# 1_ISO-RS485.net
KiCad netlist of a schematic drawn in Altium Designer
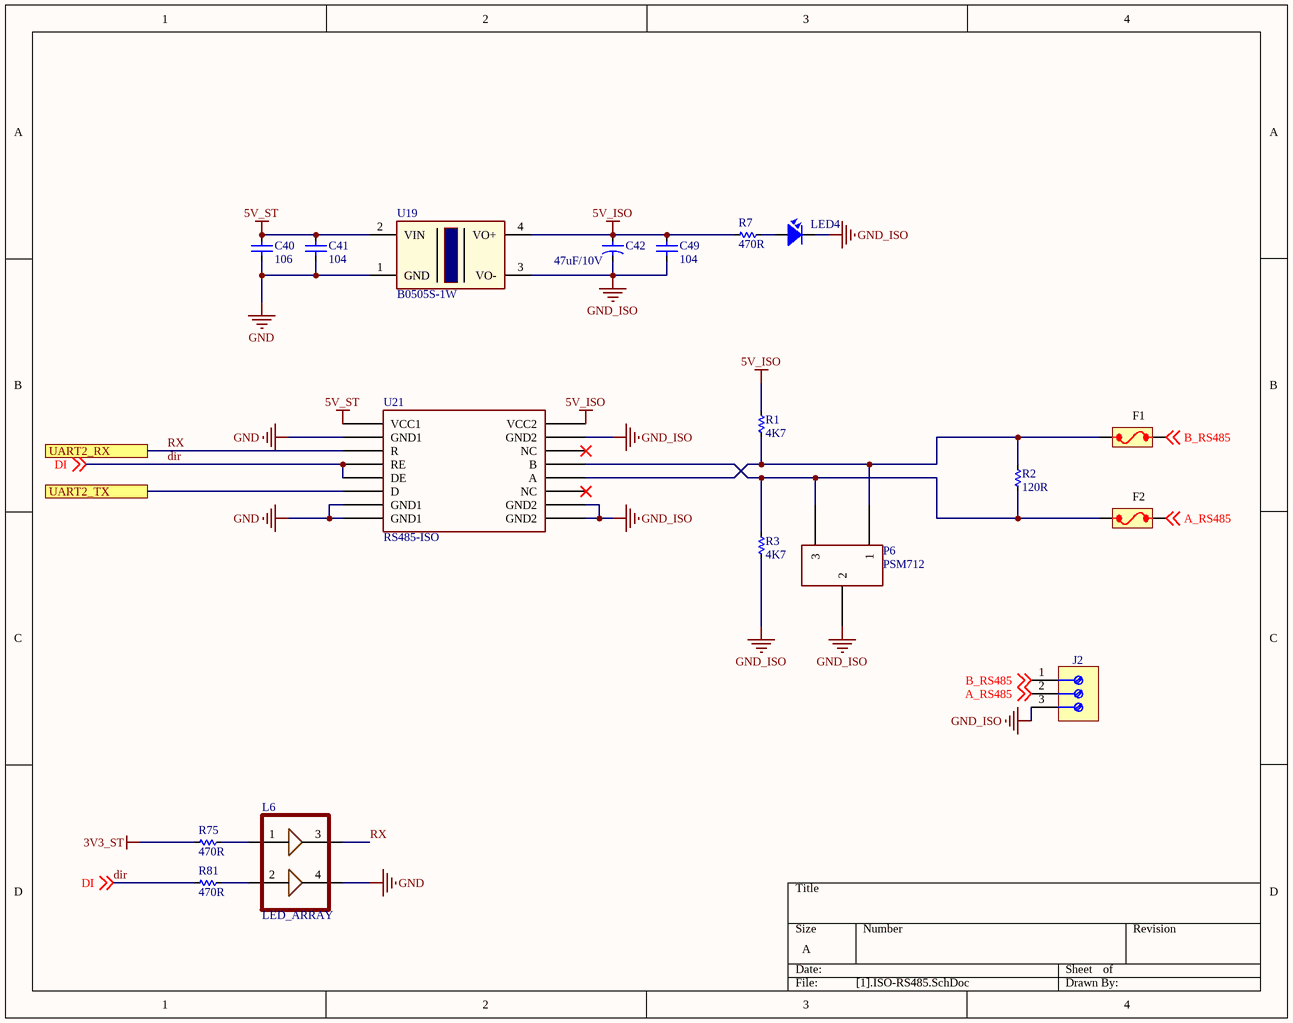
[diagram p0: [1].ISO-RS485.SchDoc]

(export (version "E")
  (design (tool "Eeschema 10.0.6"))
  (components
    (comp (ref "C40")
      (value "106")
      (footprint "CAP-1206-SC")
      (libsource (lib "QT TECH CO.,LTD") (part "CAP_NP"))
    )
    (comp (ref "C41")
      (value "104")
      (footprint "CAP-1206-SC")
      (libsource (lib "QT TECH CO.,LTD") (part "CAP_NP"))
    )
    (comp (ref "C42")
      (value "47uF/10V")
      (footprint "CAP 6.3X12X2.5")
      (libsource (lib "QT TECH CO.,LTD") (part "CAP 100uF/16V"))
    )
    (comp (ref "C49")
      (value "104")
      (footprint "CAP-1206-SC")
      (libsource (lib "QT TECH CO.,LTD") (part "CAP_NP"))
    )
    (comp (ref "F1")
      (value "FUSE")
      (footprint "FUSE_RESETTABLE_SMD_1812")
      (fields (field (name "PUBLISHER") "Hoang Nguyen"))
      (libsource (lib "Nucleo_IOT") (part "FUSE"))
    )
    (comp (ref "F2")
      (value "FUSE")
      (footprint "FUSE_RESETTABLE_SMD_1812")
      (fields (field (name "PUBLISHER") "Hoang Nguyen"))
      (libsource (lib "Nucleo_IOT") (part "FUSE"))
    )
    (comp (ref "J2")
      (value "~")
      (footprint "PHOENIX_1803439")
      (description "Terminal Block, 3 Positions, Screw Connection")
      (libsource (lib "SCH_NHATBON") (part "Terminal Block_3 Positions_Screw Connection"))
    )
    (comp (ref "L6")
      (value "LED_ARRAY")
      (footprint "LED_ARRAY2")
      (libsource (lib "LED_ARRAY_2") (part "LED_ARRAY"))
    )
    (comp (ref "LED4")
      (value "LED RED 3mm")
      (footprint "LED-3MM-RED")
      (description "LED Single colour Green and Red")
      (libsource (lib "LIBRARY") (part "LED"))
    )
    (comp (ref "P6") (value "PSM712") (footprint "SOT23C") (libsource (lib "PSM712") (part "PSM712")))
    (comp (ref "R1")
      (value "4K7")
      (footprint "RES-SMD-0805")
      (description "Resistor")
      (fields
        (field (name "MANUFACTURER") "Generic Components")
        (field (name "PUBLISHER") "Altium Hobart Technology Centre")
      )
      (libsource (lib "LIBRARY") (part "Res-SMD"))
    )
    (comp (ref "R2")
      (value "120R")
      (footprint "RES-SMD-0805")
      (description "Resistor")
      (fields
        (field (name "MANUFACTURER") "Generic Components")
        (field (name "PUBLISHER") "Altium Hobart Technology Centre")
      )
      (libsource (lib "LIBRARY") (part "Res-SMD"))
    )
    (comp (ref "R3")
      (value "4K7")
      (footprint "RES-SMD-0805")
      (description "Resistor")
      (fields
        (field (name "MANUFACTURER") "Generic Components")
        (field (name "PUBLISHER") "Altium Hobart Technology Centre")
      )
      (libsource (lib "LIBRARY") (part "Res-SMD"))
    )
    (comp (ref "R7")
      (value "470R")
      (footprint "RES-SMD-0805")
      (description "Resistor")
      (fields
        (field (name "MANUFACTURER") "Generic Components")
        (field (name "PUBLISHER") "Altium Hobart Technology Centre")
      )
      (libsource (lib "LIBRARY") (part "Res-SMD"))
    )
    (comp (ref "R75")
      (value "470R")
      (footprint "RES-SMD-0805")
      (description "Resistor")
      (fields
        (field (name "MANUFACTURER") "Generic Components")
        (field (name "PUBLISHER") "Altium Hobart Technology Centre")
      )
      (libsource (lib "LIBRARY") (part "Res-SMD"))
    )
    (comp (ref "R81")
      (value "470R")
      (footprint "RES-SMD-0805")
      (description "Resistor")
      (fields
        (field (name "MANUFACTURER") "Generic Components")
        (field (name "PUBLISHER") "Altium Hobart Technology Centre")
      )
      (libsource (lib "LIBRARY") (part "Res-SMD"))
    )
    (comp (ref "U19")
      (value "B0505S-1W")
      (footprint "B0505S_1W")
      (libsource (lib "Nucleo_IOT") (part "B0505S-1W"))
    )
    (comp (ref "U21")
      (value "RS485-ISO")
      (footprint "SOIC127P1030X265-16N")
      (libsource (lib "RS485ISO") (part "RS485-ISO"))
    )
  )
  (nets
    (net (code "1") (name "/RX") (class "Default")
      (node (ref "L6") (pin "3") (pinfunction "3_3") (pintype "passive"))
      (node (ref "U21") (pin "3") (pinfunction "R_3") (pintype "passive"))
    )
    (net (code "2") (name "/UART2_TX") (class "Default")
      (node (ref "U21") (pin "6") (pinfunction "D_6") (pintype "passive"))
    )
    (net (code "3") (name "3V3_ST") (class "Default")
      (node (ref "R75") (pin "2") (pinfunction "2_2") (pintype "passive"))
    )
    (net (code "4") (name "5V_ISO") (class "Default")
      (node (ref "C42") (pin "1") (pinfunction "1_1") (pintype "passive"))
      (node (ref "C49") (pin "1") (pinfunction "1_1") (pintype "passive"))
      (node (ref "R1") (pin "2") (pinfunction "2_2") (pintype "passive"))
      (node (ref "R7") (pin "2") (pinfunction "2_2") (pintype "passive"))
      (node (ref "U19") (pin "4") (pinfunction "VO+_4") (pintype "passive"))
      (node (ref "U21") (pin "16") (pinfunction "VCC2_16") (pintype "passive"))
    )
    (net (code "5") (name "5V_ST") (class "Default")
      (node (ref "C40") (pin "1") (pinfunction "1_1") (pintype "passive"))
      (node (ref "C41") (pin "1") (pinfunction "1_1") (pintype "passive"))
      (node (ref "U19") (pin "2") (pinfunction "VIN_2") (pintype "power_in"))
      (node (ref "U21") (pin "1") (pinfunction "VCC1_1") (pintype "passive"))
    )
    (net (code "6") (name "A_RS485") (class "Default")
      (node (ref "F2") (pin "2") (pinfunction "2_2") (pintype "passive"))
      (node (ref "J2") (pin "2") (pinfunction "2_2") (pintype "passive"))
    )
    (net (code "7") (name "B_RS485") (class "Default")
      (node (ref "F1") (pin "2") (pinfunction "2_2") (pintype "passive"))
      (node (ref "J2") (pin "1") (pinfunction "1_1") (pintype "passive"))
    )
    (net (code "8") (name "DI") (class "Default")
      (node (ref "R81") (pin "2") (pinfunction "2_2") (pintype "passive"))
      (node (ref "U21") (pin "4") (pinfunction "RE_4") (pintype "passive"))
      (node (ref "U21") (pin "5") (pinfunction "DE_5") (pintype "passive"))
    )
    (net (code "9") (name "GND") (class "Default")
      (node (ref "C40") (pin "2") (pinfunction "2_2") (pintype "passive"))
      (node (ref "C41") (pin "2") (pinfunction "2_2") (pintype "passive"))
      (node (ref "L6") (pin "4") (pinfunction "3_4") (pintype "passive"))
      (node (ref "U19") (pin "1") (pinfunction "GND_1") (pintype "power_in"))
      (node (ref "U21") (pin "2") (pinfunction "GND1_2") (pintype "passive"))
      (node (ref "U21") (pin "7") (pinfunction "GND1_7") (pintype "passive"))
      (node (ref "U21") (pin "8") (pinfunction "GND1_8") (pintype "passive"))
    )
    (net (code "10") (name "GND_ISO") (class "Default")
      (node (ref "C42") (pin "2") (pinfunction "2_2") (pintype "passive"))
      (node (ref "C49") (pin "2") (pinfunction "2_2") (pintype "passive"))
      (node (ref "J2") (pin "3") (pinfunction "3_3") (pintype "passive"))
      (node (ref "LED4") (pin "2") (pinfunction "2_2") (pintype "passive"))
      (node (ref "P6") (pin "2") (pinfunction "2_2") (pintype "passive"))
      (node (ref "R3") (pin "1") (pinfunction "1_1") (pintype "passive"))
      (node (ref "U19") (pin "3") (pinfunction "VO-_3") (pintype "passive"))
      (node (ref "U21") (pin "10") (pinfunction "GND2_10") (pintype "passive"))
      (node (ref "U21") (pin "15") (pinfunction "GND2_15") (pintype "passive"))
      (node (ref "U21") (pin "9") (pinfunction "GND2_9") (pintype "passive"))
    )
    (net (code "11") (name "Net-(L6-Pad1)") (class "Default")
      (node (ref "L6") (pin "1") (pinfunction "1_1") (pintype "passive"))
      (node (ref "R75") (pin "1") (pinfunction "1_1") (pintype "passive"))
    )
    (net (code "12") (name "Net-(L6-Pad2)") (class "Default")
      (node (ref "L6") (pin "2") (pinfunction "2_2") (pintype "passive"))
      (node (ref "R81") (pin "1") (pinfunction "1_1") (pintype "passive"))
    )
    (net (code "13") (name "Net-(LED4-Pad1)") (class "Default")
      (node (ref "LED4") (pin "1") (pinfunction "1_1") (pintype "passive"))
      (node (ref "R7") (pin "1") (pinfunction "1_1") (pintype "passive"))
    )
    (net (code "14") (name "Net-(U21-A)") (class "Default")
      (node (ref "F1") (pin "1") (pinfunction "1_1") (pintype "passive"))
      (node (ref "P6") (pin "1") (pinfunction "1_1") (pintype "passive"))
      (node (ref "R1") (pin "1") (pinfunction "1_1") (pintype "passive"))
      (node (ref "R2") (pin "2") (pinfunction "2_2") (pintype "passive"))
      (node (ref "U21") (pin "12") (pinfunction "A_12") (pintype "passive"))
    )
    (net (code "15") (name "Net-(U21-B)") (class "Default")
      (node (ref "F2") (pin "1") (pinfunction "1_1") (pintype "passive"))
      (node (ref "P6") (pin "3") (pinfunction "3_3") (pintype "passive"))
      (node (ref "R2") (pin "1") (pinfunction "1_1") (pintype "passive"))
      (node (ref "R3") (pin "2") (pinfunction "2_2") (pintype "passive"))
      (node (ref "U21") (pin "13") (pinfunction "B_13") (pintype "passive"))
    )
    (net (code "16") (name "unconnected-(U21-NC-Pad11)") (class "Default")
      (node (ref "U21") (pin "11") (pinfunction "NC_11") (pintype "passive+no_connect"))
    )
    (net (code "17") (name "unconnected-(U21-NC-Pad14)") (class "Default")
      (node (ref "U21") (pin "14") (pinfunction "NC_14") (pintype "passive+no_connect"))
    )
  )
)
